# m921-submixer.net
KiCad netlist of a schematic drawn in EAGLE
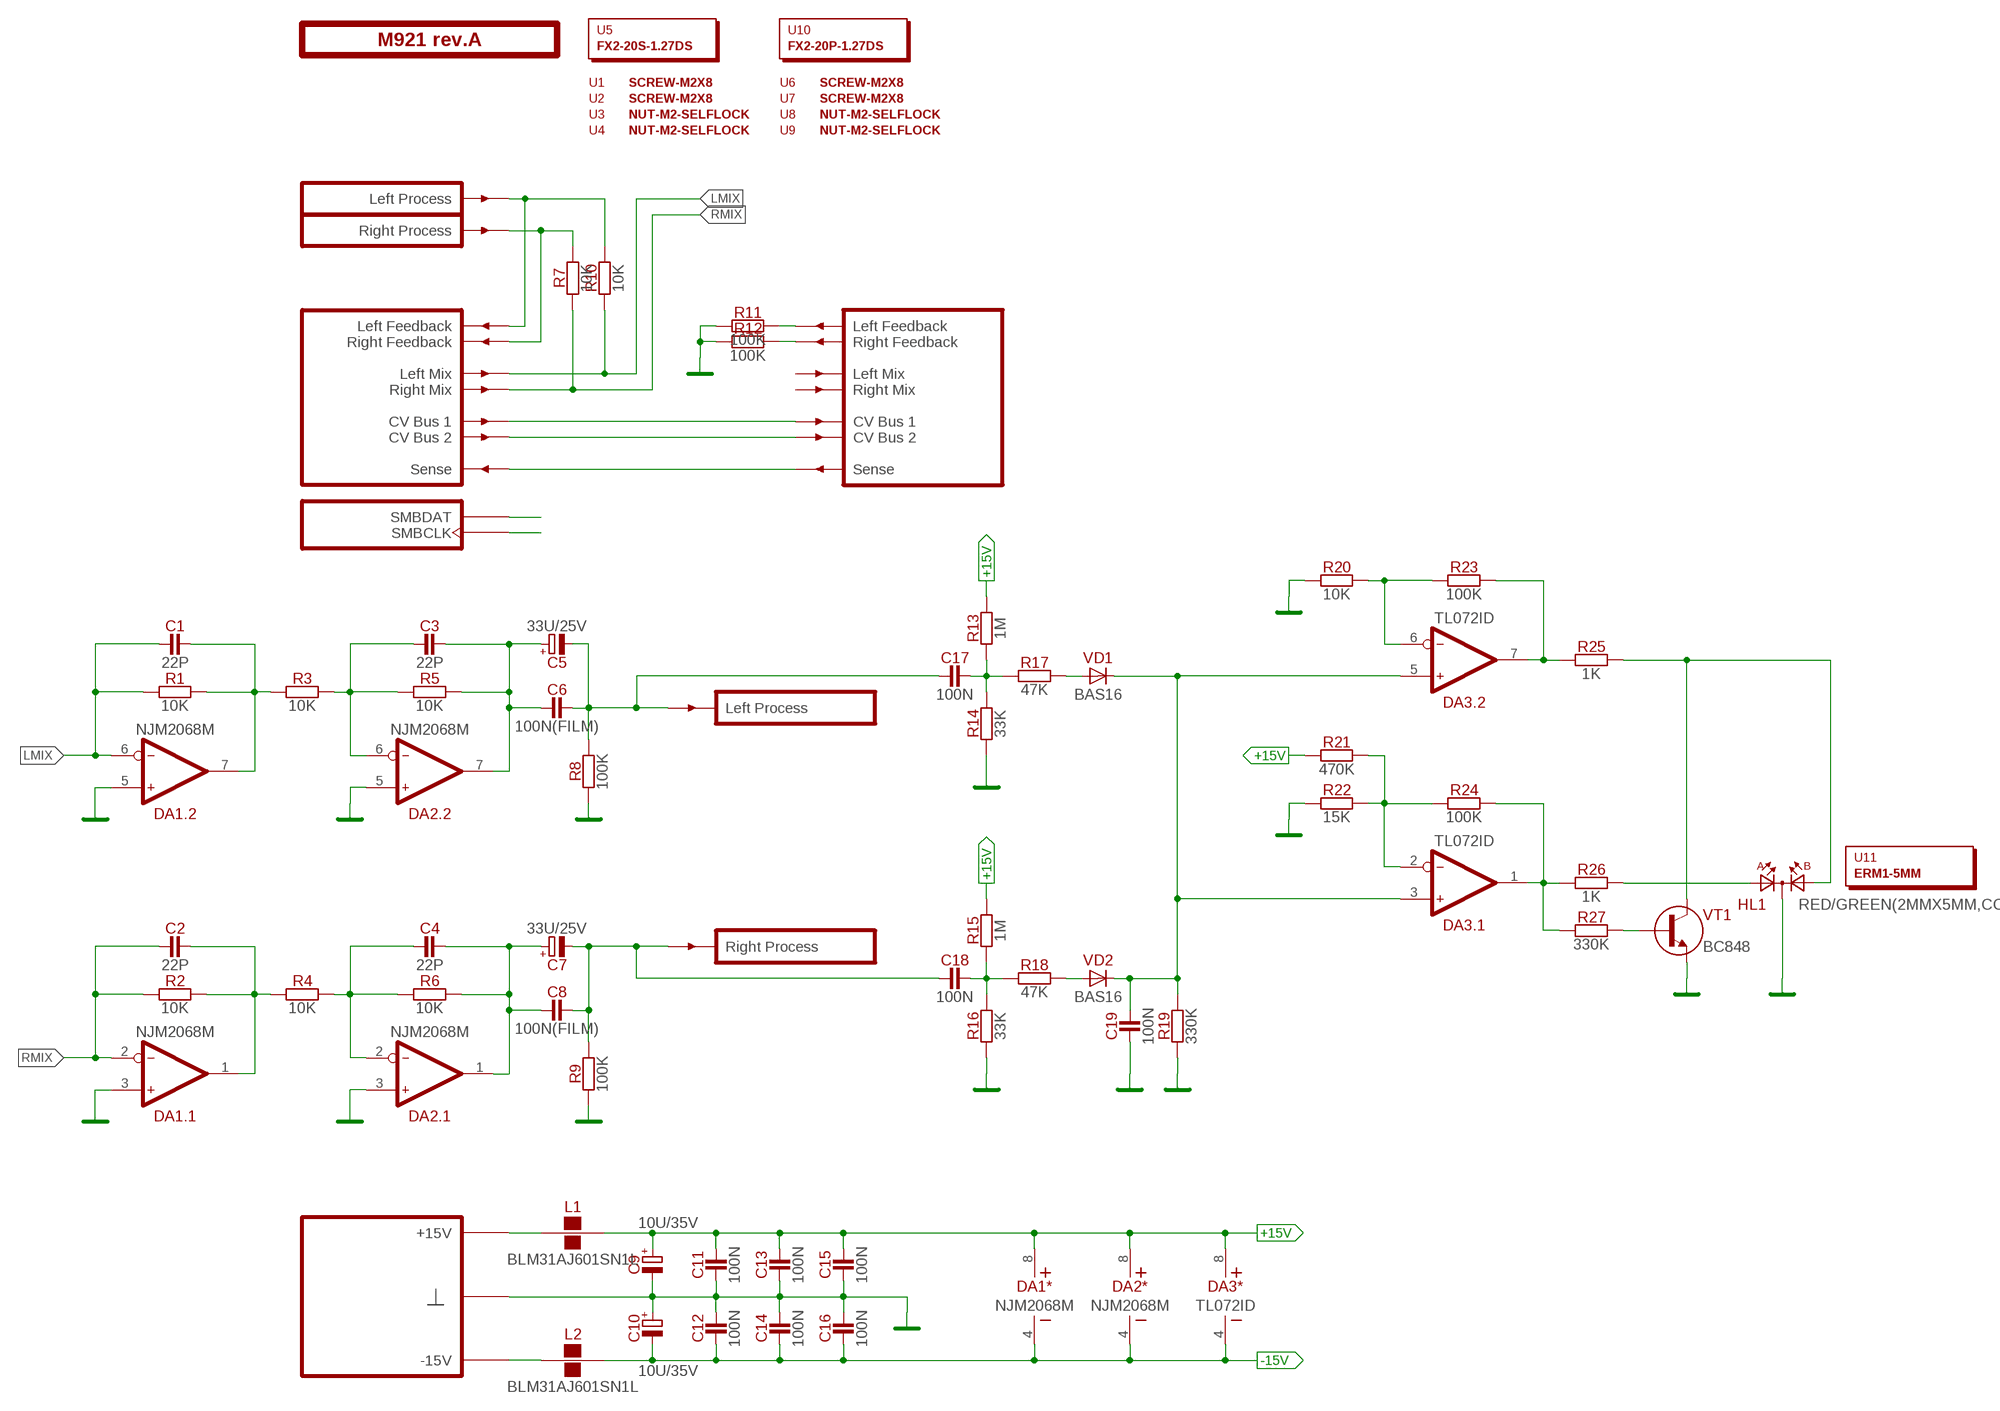
[diagram p0: schematic, sheet 1]

(export (version "E")
  (design (tool "Eeschema 10.0.6"))
  (components
    (comp (ref "C1")
      (value "22P")
      (footprint "eagle-import:C-0805")
      (libsource (lib "eagle-import") (part "?22P"))
    )
    (comp (ref "C2")
      (value "22P")
      (footprint "eagle-import:C-0805")
      (libsource (lib "eagle-import") (part "?22P"))
    )
    (comp (ref "C3")
      (value "22P")
      (footprint "eagle-import:C-0805")
      (libsource (lib "eagle-import") (part "?22P"))
    )
    (comp (ref "C4")
      (value "22P")
      (footprint "eagle-import:C-0805")
      (libsource (lib "eagle-import") (part "?22P"))
    )
    (comp (ref "C5")
      (value "33U/25V")
      (footprint "eagle-import:E2,5-7")
      (libsource (lib "eagle-import") (part "?33U/25V"))
    )
    (comp (ref "C6")
      (value "100N(FILM)")
      (footprint "eagle-import:C050-025X075")
      (libsource (lib "eagle-import") (part "?100N(FILM)"))
    )
    (comp (ref "C7")
      (value "33U/25V")
      (footprint "eagle-import:E2,5-7")
      (libsource (lib "eagle-import") (part "?33U/25V"))
    )
    (comp (ref "C8")
      (value "100N(FILM)")
      (footprint "eagle-import:C050-025X075")
      (libsource (lib "eagle-import") (part "?100N(FILM)"))
    )
    (comp (ref "C9")
      (value "10U/35V")
      (footprint "eagle-import:E2-5")
      (libsource (lib "eagle-import") (part "?10U/35V"))
    )
    (comp (ref "C10")
      (value "10U/35V")
      (footprint "eagle-import:E2-5")
      (libsource (lib "eagle-import") (part "?10U/35V"))
    )
    (comp (ref "C11")
      (value "100N")
      (footprint "eagle-import:C-0805")
      (libsource (lib "eagle-import") (part "?100N"))
    )
    (comp (ref "C12")
      (value "100N")
      (footprint "eagle-import:C-0805")
      (libsource (lib "eagle-import") (part "?100N"))
    )
    (comp (ref "C13")
      (value "100N")
      (footprint "eagle-import:C-0805")
      (libsource (lib "eagle-import") (part "?100N"))
    )
    (comp (ref "C14")
      (value "100N")
      (footprint "eagle-import:C-0805")
      (libsource (lib "eagle-import") (part "?100N"))
    )
    (comp (ref "C15")
      (value "100N")
      (footprint "eagle-import:C-0805")
      (libsource (lib "eagle-import") (part "?100N"))
    )
    (comp (ref "C16")
      (value "100N")
      (footprint "eagle-import:C-0805")
      (libsource (lib "eagle-import") (part "?100N"))
    )
    (comp (ref "C17")
      (value "100N")
      (footprint "eagle-import:C-0805")
      (libsource (lib "eagle-import") (part "?100N"))
    )
    (comp (ref "C18")
      (value "100N")
      (footprint "eagle-import:C-0805")
      (libsource (lib "eagle-import") (part "?100N"))
    )
    (comp (ref "C19")
      (value "100N")
      (footprint "eagle-import:C-0805")
      (libsource (lib "eagle-import") (part "?100N"))
    )
    (comp (ref "DA1")
      (value "NJM2068M")
      (footprint "eagle-import:SO-8")
      (libsource (lib "eagle-import") (part "NJM2068M"))
    )
    (comp (ref "DA2")
      (value "NJM2068M")
      (footprint "eagle-import:SO-8")
      (libsource (lib "eagle-import") (part "NJM2068M"))
    )
    (comp (ref "DA3")
      (value "TL072ID")
      (footprint "eagle-import:SO-8")
      (libsource (lib "eagle-import") (part "TL072ID"))
    )
    (comp (ref "HL1")
      (value "RED/GREEN(2MMX5MM,CC)")
      (footprint "eagle-import:LED2X5-3PIN")
      (libsource (lib "eagle-import") (part "?(2MMX5MM,CC)RED/GREEN"))
    )
    (comp (ref "L1")
      (value "BLM31AJ601SN1L")
      (footprint "eagle-import:1206")
      (libsource (lib "eagle-import") (part "BLM31AJ601SN1L"))
    )
    (comp (ref "L2")
      (value "BLM31AJ601SN1L")
      (footprint "eagle-import:1206")
      (libsource (lib "eagle-import") (part "BLM31AJ601SN1L"))
    )
    (comp (ref "PCB1")
      (value "M921 rev.A")
      (footprint "eagle-import:ST2-BOARD-26")
      (libsource (lib "eagle-import") (part "ST2-BOARD-?26"))
    )
    (comp (ref "R1")
      (value "10K")
      (footprint "eagle-import:R-0805")
      (libsource (lib "eagle-import") (part "?10K"))
    )
    (comp (ref "R2")
      (value "10K")
      (footprint "eagle-import:R-0805")
      (libsource (lib "eagle-import") (part "?10K"))
    )
    (comp (ref "R3")
      (value "10K")
      (footprint "eagle-import:R-0805")
      (libsource (lib "eagle-import") (part "?10K"))
    )
    (comp (ref "R4")
      (value "10K")
      (footprint "eagle-import:R-0805")
      (libsource (lib "eagle-import") (part "?10K"))
    )
    (comp (ref "R5")
      (value "10K")
      (footprint "eagle-import:R-0805")
      (libsource (lib "eagle-import") (part "?10K"))
    )
    (comp (ref "R6")
      (value "10K")
      (footprint "eagle-import:R-0805")
      (libsource (lib "eagle-import") (part "?10K"))
    )
    (comp (ref "R7")
      (value "10K")
      (footprint "eagle-import:R-0805")
      (libsource (lib "eagle-import") (part "?10K"))
    )
    (comp (ref "R8")
      (value "100K")
      (footprint "eagle-import:R-0805")
      (libsource (lib "eagle-import") (part "?100K"))
    )
    (comp (ref "R9")
      (value "100K")
      (footprint "eagle-import:R-0805")
      (libsource (lib "eagle-import") (part "?100K"))
    )
    (comp (ref "R10")
      (value "10K")
      (footprint "eagle-import:R-0805")
      (libsource (lib "eagle-import") (part "?10K"))
    )
    (comp (ref "R11")
      (value "100K")
      (footprint "eagle-import:R-0805")
      (libsource (lib "eagle-import") (part "?100K"))
    )
    (comp (ref "R12")
      (value "100K")
      (footprint "eagle-import:R-0805")
      (libsource (lib "eagle-import") (part "?100K"))
    )
    (comp (ref "R13")
      (value "1M")
      (footprint "eagle-import:R-0805")
      (libsource (lib "eagle-import") (part "?1M"))
    )
    (comp (ref "R14")
      (value "33K")
      (footprint "eagle-import:R-0805")
      (libsource (lib "eagle-import") (part "?33K"))
    )
    (comp (ref "R15")
      (value "1M")
      (footprint "eagle-import:R-0805")
      (libsource (lib "eagle-import") (part "?1M"))
    )
    (comp (ref "R16")
      (value "33K")
      (footprint "eagle-import:R-0805")
      (libsource (lib "eagle-import") (part "?33K"))
    )
    (comp (ref "R17")
      (value "47K")
      (footprint "eagle-import:R-0805")
      (libsource (lib "eagle-import") (part "?47K"))
    )
    (comp (ref "R18")
      (value "47K")
      (footprint "eagle-import:R-0805")
      (libsource (lib "eagle-import") (part "?47K"))
    )
    (comp (ref "R19")
      (value "330K")
      (footprint "eagle-import:R-0805")
      (libsource (lib "eagle-import") (part "?330K"))
    )
    (comp (ref "R20")
      (value "10K")
      (footprint "eagle-import:R-0805")
      (libsource (lib "eagle-import") (part "?10K"))
    )
    (comp (ref "R21")
      (value "470K")
      (footprint "eagle-import:R-0805")
      (libsource (lib "eagle-import") (part "?470K"))
    )
    (comp (ref "R22")
      (value "15K")
      (footprint "eagle-import:R-0805")
      (libsource (lib "eagle-import") (part "?15K"))
    )
    (comp (ref "R23")
      (value "100K")
      (footprint "eagle-import:R-0805")
      (libsource (lib "eagle-import") (part "?100K"))
    )
    (comp (ref "R24")
      (value "100K")
      (footprint "eagle-import:R-0805")
      (libsource (lib "eagle-import") (part "?100K"))
    )
    (comp (ref "R25")
      (value "1K")
      (footprint "eagle-import:R-0805")
      (libsource (lib "eagle-import") (part "?1K"))
    )
    (comp (ref "R26")
      (value "1K")
      (footprint "eagle-import:R-0805")
      (libsource (lib "eagle-import") (part "?1K"))
    )
    (comp (ref "R27")
      (value "330K")
      (footprint "eagle-import:R-0805")
      (libsource (lib "eagle-import") (part "?330K"))
    )
    (comp (ref "U1")
      (value "SCREW-M2X8")
      (footprint "eagle-import:EMPTY")
      (libsource (lib "eagle-import") (part "?SCREW-M2X8"))
    )
    (comp (ref "U2")
      (value "SCREW-M2X8")
      (footprint "eagle-import:EMPTY")
      (libsource (lib "eagle-import") (part "?SCREW-M2X8"))
    )
    (comp (ref "U3")
      (value "NUT-M2-SELFLOCK")
      (footprint "eagle-import:EMPTY")
      (libsource (lib "eagle-import") (part "?NUT-M2-SELFLOCK"))
    )
    (comp (ref "U4")
      (value "NUT-M2-SELFLOCK")
      (footprint "eagle-import:EMPTY")
      (libsource (lib "eagle-import") (part "?NUT-M2-SELFLOCK"))
    )
    (comp (ref "U5")
      (value "FX2-20S-1.27DS")
      (footprint "eagle-import:EMPTY")
      (libsource (lib "eagle-import") (part "?FX2-20S-1.27DS"))
    )
    (comp (ref "U6")
      (value "SCREW-M2X8")
      (footprint "eagle-import:EMPTY")
      (libsource (lib "eagle-import") (part "?SCREW-M2X8"))
    )
    (comp (ref "U7")
      (value "SCREW-M2X8")
      (footprint "eagle-import:EMPTY")
      (libsource (lib "eagle-import") (part "?SCREW-M2X8"))
    )
    (comp (ref "U8")
      (value "NUT-M2-SELFLOCK")
      (footprint "eagle-import:EMPTY")
      (libsource (lib "eagle-import") (part "?NUT-M2-SELFLOCK"))
    )
    (comp (ref "U9")
      (value "NUT-M2-SELFLOCK")
      (footprint "eagle-import:EMPTY")
      (libsource (lib "eagle-import") (part "?NUT-M2-SELFLOCK"))
    )
    (comp (ref "U10")
      (value "FX2-20P-1.27DS")
      (footprint "eagle-import:EMPTY")
      (libsource (lib "eagle-import") (part "?FX2-20P-1.27DS"))
    )
    (comp (ref "U11")
      (value "ERM1-5MM")
      (footprint "eagle-import:EMPTY")
      (libsource (lib "eagle-import") (part "?ERM1-5MM"))
    )
    (comp (ref "VD1")
      (value "BAS16")
      (footprint "eagle-import:SOT23")
      (libsource (lib "eagle-import") (part "?BAS16"))
    )
    (comp (ref "VD2")
      (value "BAS16")
      (footprint "eagle-import:SOT23")
      (libsource (lib "eagle-import") (part "?BAS16"))
    )
    (comp (ref "VT1")
      (value "BC848")
      (footprint "eagle-import:SOT23")
      (libsource (lib "eagle-import") (part "?BC848"))
    )
  )
  (nets
    (net (code "1") (name "+15V") (class "Default")
      (node (ref "C11") (pin "2") (pinfunction "2_2") (pintype "passive"))
      (node (ref "C13") (pin "2") (pinfunction "2_2") (pintype "passive"))
      (node (ref "C15") (pin "2") (pinfunction "2_2") (pintype "passive"))
      (node (ref "C9") (pin "+") (pinfunction "+_+") (pintype "passive"))
      (node (ref "DA1") (pin "8") (pinfunction "V+_8") (pintype "power_in"))
      (node (ref "DA2") (pin "8") (pinfunction "V+_8") (pintype "power_in"))
      (node (ref "DA3") (pin "8") (pinfunction "V+_8") (pintype "power_in"))
      (node (ref "L1") (pin "2") (pinfunction "2_2") (pintype "passive"))
      (node (ref "R13") (pin "2") (pinfunction "2_2") (pintype "passive"))
      (node (ref "R15") (pin "2") (pinfunction "2_2") (pintype "passive"))
      (node (ref "R21") (pin "1") (pinfunction "1_1") (pintype "passive"))
    )
    (net (code "2") (name "-15V") (class "Default")
      (node (ref "C10") (pin "-") (pinfunction "-_-") (pintype "passive"))
      (node (ref "C12") (pin "1") (pinfunction "1_1") (pintype "passive"))
      (node (ref "C14") (pin "1") (pinfunction "1_1") (pintype "passive"))
      (node (ref "C16") (pin "1") (pinfunction "1_1") (pintype "passive"))
      (node (ref "DA1") (pin "4") (pinfunction "V-_4") (pintype "power_in"))
      (node (ref "DA2") (pin "4") (pinfunction "V-_4") (pintype "power_in"))
      (node (ref "DA3") (pin "4") (pinfunction "V-_4") (pintype "power_in"))
      (node (ref "L2") (pin "2") (pinfunction "2_2") (pintype "passive"))
    )
    (net (code "3") (name "GND") (class "Default")
      (node (ref "C10") (pin "+") (pinfunction "+_+") (pintype "passive"))
      (node (ref "C11") (pin "1") (pinfunction "1_1") (pintype "passive"))
      (node (ref "C12") (pin "2") (pinfunction "2_2") (pintype "passive"))
      (node (ref "C13") (pin "1") (pinfunction "1_1") (pintype "passive"))
      (node (ref "C14") (pin "2") (pinfunction "2_2") (pintype "passive"))
      (node (ref "C15") (pin "1") (pinfunction "1_1") (pintype "passive"))
      (node (ref "C16") (pin "2") (pinfunction "2_2") (pintype "passive"))
      (node (ref "C19") (pin "1") (pinfunction "1_1") (pintype "passive"))
      (node (ref "C9") (pin "-") (pinfunction "-_-") (pintype "passive"))
      (node (ref "DA1") (pin "3") (pinfunction "IN+_3") (pintype "input"))
      (node (ref "DA1") (pin "5") (pinfunction "IN+_5") (pintype "input"))
      (node (ref "DA2") (pin "3") (pinfunction "IN+_3") (pintype "input"))
      (node (ref "DA2") (pin "5") (pinfunction "IN+_5") (pintype "input"))
      (node (ref "HL1") (pin "K") (pinfunction "K_K") (pintype "passive"))
      (node (ref "PCB1") (pin "B4") (pinfunction "GND_B4") (pintype "bidirectional"))
      (node (ref "PCB1") (pin "B4'") (pinfunction "GND_B4'") (pintype "bidirectional"))
      (node (ref "PCB1") (pin "B5") (pinfunction "GND_B5") (pintype "bidirectional"))
      (node (ref "PCB1") (pin "B5'") (pinfunction "GND_B5'") (pintype "bidirectional"))
      (node (ref "PCB1") (pin "B6") (pinfunction "GND_B6") (pintype "bidirectional"))
      (node (ref "PCB1") (pin "B6'") (pinfunction "GND_B6'") (pintype "bidirectional"))
      (node (ref "PCB1") (pin "B7") (pinfunction "GND_B7") (pintype "bidirectional"))
      (node (ref "PCB1") (pin "B7'") (pinfunction "GND_B7'") (pintype "bidirectional"))
      (node (ref "PCB1") (pin "B8") (pinfunction "GND_B8") (pintype "bidirectional"))
      (node (ref "PCB1") (pin "B8'") (pinfunction "GND_B8'") (pintype "bidirectional"))
      (node (ref "R11") (pin "1") (pinfunction "1_1") (pintype "passive"))
      (node (ref "R12") (pin "1") (pinfunction "1_1") (pintype "passive"))
      (node (ref "R14") (pin "1") (pinfunction "1_1") (pintype "passive"))
      (node (ref "R16") (pin "1") (pinfunction "1_1") (pintype "passive"))
      (node (ref "R19") (pin "1") (pinfunction "1_1") (pintype "passive"))
      (node (ref "R20") (pin "1") (pinfunction "1_1") (pintype "passive"))
      (node (ref "R22") (pin "1") (pinfunction "1_1") (pintype "passive"))
      (node (ref "R8") (pin "1") (pinfunction "1_1") (pintype "passive"))
      (node (ref "R9") (pin "1") (pinfunction "1_1") (pintype "passive"))
      (node (ref "VT1") (pin "2") (pinfunction "E_2") (pintype "passive"))
    )
    (net (code "4") (name "LMIX") (class "Default")
      (node (ref "C1") (pin "1") (pinfunction "1_1") (pintype "passive"))
      (node (ref "DA1") (pin "6") (pinfunction "IN-_6") (pintype "input"))
      (node (ref "PCB1") (pin "ALMIX") (pinfunction "LMIX_ALMIX") (pintype "bidirectional"))
      (node (ref "R1") (pin "1") (pinfunction "1_1") (pintype "passive"))
      (node (ref "R10") (pin "1") (pinfunction "1_1") (pintype "passive"))
    )
    (net (code "5") (name "Net-(C17-Pad2)") (class "Default")
      (node (ref "C17") (pin "2") (pinfunction "2_2") (pintype "passive"))
      (node (ref "R13") (pin "1") (pinfunction "1_1") (pintype "passive"))
      (node (ref "R14") (pin "2") (pinfunction "2_2") (pintype "passive"))
      (node (ref "R17") (pin "1") (pinfunction "1_1") (pintype "passive"))
    )
    (net (code "6") (name "Net-(C18-Pad2)") (class "Default")
      (node (ref "C18") (pin "2") (pinfunction "2_2") (pintype "passive"))
      (node (ref "R15") (pin "1") (pinfunction "1_1") (pintype "passive"))
      (node (ref "R16") (pin "2") (pinfunction "2_2") (pintype "passive"))
      (node (ref "R18") (pin "1") (pinfunction "1_1") (pintype "passive"))
    )
    (net (code "7") (name "Net-(DA1B-OUT)") (class "Default")
      (node (ref "C2") (pin "2") (pinfunction "2_2") (pintype "passive"))
      (node (ref "DA1") (pin "1") (pinfunction "OUT_1") (pintype "output"))
      (node (ref "R2") (pin "2") (pinfunction "2_2") (pintype "passive"))
      (node (ref "R4") (pin "1") (pinfunction "1_1") (pintype "passive"))
    )
    (net (code "8") (name "Net-(DA1C-OUT)") (class "Default")
      (node (ref "C1") (pin "2") (pinfunction "2_2") (pintype "passive"))
      (node (ref "DA1") (pin "7") (pinfunction "OUT_7") (pintype "output"))
      (node (ref "R1") (pin "2") (pinfunction "2_2") (pintype "passive"))
      (node (ref "R3") (pin "1") (pinfunction "1_1") (pintype "passive"))
    )
    (net (code "9") (name "Net-(DA2B-IN-)") (class "Default")
      (node (ref "C4") (pin "1") (pinfunction "1_1") (pintype "passive"))
      (node (ref "DA2") (pin "2") (pinfunction "IN-_2") (pintype "input"))
      (node (ref "R4") (pin "2") (pinfunction "2_2") (pintype "passive"))
      (node (ref "R6") (pin "1") (pinfunction "1_1") (pintype "passive"))
    )
    (net (code "10") (name "Net-(DA2B-OUT)") (class "Default")
      (node (ref "C4") (pin "2") (pinfunction "2_2") (pintype "passive"))
      (node (ref "C7") (pin "+") (pinfunction "+_+") (pintype "passive"))
      (node (ref "C8") (pin "1") (pinfunction "1_1") (pintype "passive"))
      (node (ref "DA2") (pin "1") (pinfunction "OUT_1") (pintype "output"))
      (node (ref "R6") (pin "2") (pinfunction "2_2") (pintype "passive"))
    )
    (net (code "11") (name "Net-(DA2C-IN-)") (class "Default")
      (node (ref "C3") (pin "1") (pinfunction "1_1") (pintype "passive"))
      (node (ref "DA2") (pin "6") (pinfunction "IN-_6") (pintype "input"))
      (node (ref "R3") (pin "2") (pinfunction "2_2") (pintype "passive"))
      (node (ref "R5") (pin "1") (pinfunction "1_1") (pintype "passive"))
    )
    (net (code "12") (name "Net-(DA2C-OUT)") (class "Default")
      (node (ref "C3") (pin "2") (pinfunction "2_2") (pintype "passive"))
      (node (ref "C5") (pin "+") (pinfunction "+_+") (pintype "passive"))
      (node (ref "C6") (pin "1") (pinfunction "1_1") (pintype "passive"))
      (node (ref "DA2") (pin "7") (pinfunction "OUT_7") (pintype "output"))
      (node (ref "R5") (pin "2") (pinfunction "2_2") (pintype "passive"))
    )
    (net (code "13") (name "Net-(DA3B-IN+)") (class "Default")
      (node (ref "C19") (pin "2") (pinfunction "2_2") (pintype "passive"))
      (node (ref "DA3") (pin "3") (pinfunction "IN+_3") (pintype "input"))
      (node (ref "DA3") (pin "5") (pinfunction "IN+_5") (pintype "input"))
      (node (ref "R19") (pin "2") (pinfunction "2_2") (pintype "passive"))
      (node (ref "VD1") (pin "2") (pinfunction "C_2") (pintype "passive"))
      (node (ref "VD2") (pin "2") (pinfunction "C_2") (pintype "passive"))
    )
    (net (code "14") (name "Net-(DA3B-IN-)") (class "Default")
      (node (ref "DA3") (pin "2") (pinfunction "IN-_2") (pintype "input"))
      (node (ref "R21") (pin "2") (pinfunction "2_2") (pintype "passive"))
      (node (ref "R22") (pin "2") (pinfunction "2_2") (pintype "passive"))
      (node (ref "R24") (pin "1") (pinfunction "1_1") (pintype "passive"))
    )
    (net (code "15") (name "Net-(DA3B-OUT)") (class "Default")
      (node (ref "DA3") (pin "1") (pinfunction "OUT_1") (pintype "output"))
      (node (ref "R24") (pin "2") (pinfunction "2_2") (pintype "passive"))
      (node (ref "R26") (pin "1") (pinfunction "1_1") (pintype "passive"))
      (node (ref "R27") (pin "1") (pinfunction "1_1") (pintype "passive"))
    )
    (net (code "16") (name "Net-(DA3C-IN-)") (class "Default")
      (node (ref "DA3") (pin "6") (pinfunction "IN-_6") (pintype "input"))
      (node (ref "R20") (pin "2") (pinfunction "2_2") (pintype "passive"))
      (node (ref "R23") (pin "1") (pinfunction "1_1") (pintype "passive"))
    )
    (net (code "17") (name "Net-(DA3C-OUT)") (class "Default")
      (node (ref "DA3") (pin "7") (pinfunction "OUT_7") (pintype "output"))
      (node (ref "R23") (pin "2") (pinfunction "2_2") (pintype "passive"))
      (node (ref "R25") (pin "1") (pinfunction "1_1") (pintype "passive"))
    )
    (net (code "18") (name "Net-(HL1-PadA1)") (class "Default")
      (node (ref "HL1") (pin "A1") (pinfunction "A1_A1") (pintype "passive"))
      (node (ref "R26") (pin "2") (pinfunction "2_2") (pintype "passive"))
    )
    (net (code "19") (name "Net-(L1-Pad1)") (class "Default")
      (node (ref "L1") (pin "1") (pinfunction "1_1") (pintype "passive"))
      (node (ref "PCB1") (pin "A+15") (pinfunction "P+15V_A+15") (pintype "bidirectional"))
      (node (ref "PCB1") (pin "A+15'") (pinfunction "P+15V_A+15'") (pintype "bidirectional"))
      (node (ref "PCB1") (pin "B+15") (pinfunction "P+15V_B+15") (pintype "bidirectional"))
      (node (ref "PCB1") (pin "B+15'") (pinfunction "P+15V_B+15'") (pintype "bidirectional"))
    )
    (net (code "20") (name "Net-(L2-Pad1)") (class "Default")
      (node (ref "L2") (pin "1") (pinfunction "1_1") (pintype "passive"))
      (node (ref "PCB1") (pin "A-15") (pinfunction "P-15V_A-15") (pintype "bidirectional"))
      (node (ref "PCB1") (pin "A-15'") (pinfunction "P-15V_A-15'") (pintype "bidirectional"))
      (node (ref "PCB1") (pin "B-15") (pinfunction "P-15V_B-15") (pintype "bidirectional"))
      (node (ref "PCB1") (pin "B-15'") (pinfunction "P-15V_B-15'") (pintype "bidirectional"))
    )
    (net (code "21") (name "Net-(PCB1B-INL)") (class "Default")
      (node (ref "PCB1") (pin "ALFBK") (pinfunction "LFBK_ALFBK") (pintype "bidirectional"))
      (node (ref "PCB1") (pin "BINL") (pinfunction "INL_BINL") (pintype "bidirectional"))
      (node (ref "R10") (pin "2") (pinfunction "2_2") (pintype "passive"))
    )
    (net (code "22") (name "Net-(PCB1C-INR)") (class "Default")
      (node (ref "PCB1") (pin "ARFBK") (pinfunction "RFBK_ARFBK") (pintype "bidirectional"))
      (node (ref "PCB1") (pin "BINR") (pinfunction "INR_BINR") (pintype "bidirectional"))
      (node (ref "R7") (pin "2") (pinfunction "2_2") (pintype "passive"))
    )
    (net (code "23") (name "Net-(PCB1D-OUTL)") (class "Default")
      (node (ref "C17") (pin "1") (pinfunction "1_1") (pintype "passive"))
      (node (ref "C5") (pin "-") (pinfunction "-_-") (pintype "passive"))
      (node (ref "C6") (pin "2") (pinfunction "2_2") (pintype "passive"))
      (node (ref "PCB1") (pin "BOUTL'") (pinfunction "OUTL_BOUTL'") (pintype "bidirectional"))
      (node (ref "R8") (pin "2") (pinfunction "2_2") (pintype "passive"))
    )
    (net (code "24") (name "Net-(PCB1E-OUTR)") (class "Default")
      (node (ref "C18") (pin "1") (pinfunction "1_1") (pintype "passive"))
      (node (ref "C7") (pin "-") (pinfunction "-_-") (pintype "passive"))
      (node (ref "C8") (pin "2") (pinfunction "2_2") (pintype "passive"))
      (node (ref "PCB1") (pin "BOUTR'") (pinfunction "OUTR_BOUTR'") (pintype "bidirectional"))
      (node (ref "R9") (pin "2") (pinfunction "2_2") (pintype "passive"))
    )
    (net (code "25") (name "Net-(PCB1F-CV1)") (class "Default")
      (node (ref "PCB1") (pin "ACV1") (pinfunction "CV1_ACV1") (pintype "bidirectional"))
      (node (ref "PCB1") (pin "ACV1'") (pinfunction "CV1'_ACV1'") (pintype "bidirectional"))
    )
    (net (code "26") (name "Net-(PCB1F-CV2)") (class "Default")
      (node (ref "PCB1") (pin "ACV2") (pinfunction "CV2_ACV2") (pintype "bidirectional"))
      (node (ref "PCB1") (pin "ACV2'") (pinfunction "CV2'_ACV2'") (pintype "bidirectional"))
    )
    (net (code "27") (name "Net-(PCB1F-SENSE)") (class "Default")
      (node (ref "PCB1") (pin "BSENSE") (pinfunction "SENSE_BSENSE") (pintype "bidirectional"))
      (node (ref "PCB1") (pin "BSENSE'") (pinfunction "SENSE'_BSENSE'") (pintype "bidirectional"))
    )
    (net (code "28") (name "Net-(PCB1G-LFBK')") (class "Default")
      (node (ref "PCB1") (pin "ALFBK'") (pinfunction "LFBK'_ALFBK'") (pintype "bidirectional"))
      (node (ref "R11") (pin "2") (pinfunction "2_2") (pintype "passive"))
    )
    (net (code "29") (name "Net-(PCB1G-RFBK')") (class "Default")
      (node (ref "PCB1") (pin "ARFBK'") (pinfunction "RFBK'_ARFBK'") (pintype "bidirectional"))
      (node (ref "R12") (pin "2") (pinfunction "2_2") (pintype "passive"))
    )
    (net (code "30") (name "Net-(PCB1H-SMBCLK-PadASMBCLK')") (class "Default")
      (node (ref "PCB1") (pin "ASMBCLK") (pinfunction "SMBCLK_ASMBCLK") (pintype "bidirectional"))
      (node (ref "PCB1") (pin "ASMBCLK'") (pinfunction "SMBCLK_ASMBCLK'") (pintype "bidirectional"))
    )
    (net (code "31") (name "Net-(PCB1H-SMBDAT-PadASMBDAT')") (class "Default")
      (node (ref "PCB1") (pin "ASMBDAT") (pinfunction "SMBDAT_ASMBDAT") (pintype "bidirectional"))
      (node (ref "PCB1") (pin "ASMBDAT'") (pinfunction "SMBDAT_ASMBDAT'") (pintype "bidirectional"))
    )
    (net (code "32") (name "Net-(VD1-A)") (class "Default")
      (node (ref "R17") (pin "2") (pinfunction "2_2") (pintype "passive"))
      (node (ref "VD1") (pin "1") (pinfunction "A_1") (pintype "passive"))
    )
    (net (code "33") (name "Net-(VD2-A)") (class "Default")
      (node (ref "R18") (pin "2") (pinfunction "2_2") (pintype "passive"))
      (node (ref "VD2") (pin "1") (pinfunction "A_1") (pintype "passive"))
    )
    (net (code "34") (name "Net-(VT1-B)") (class "Default")
      (node (ref "R27") (pin "2") (pinfunction "2_2") (pintype "passive"))
      (node (ref "VT1") (pin "1") (pinfunction "B_1") (pintype "passive"))
    )
    (net (code "35") (name "Net-(VT1-C)") (class "Default")
      (node (ref "HL1") (pin "A2") (pinfunction "A2_A2") (pintype "passive"))
      (node (ref "R25") (pin "2") (pinfunction "2_2") (pintype "passive"))
      (node (ref "VT1") (pin "3") (pinfunction "C_3") (pintype "passive"))
    )
    (net (code "36") (name "RMIX") (class "Default")
      (node (ref "C2") (pin "1") (pinfunction "1_1") (pintype "passive"))
      (node (ref "DA1") (pin "2") (pinfunction "IN-_2") (pintype "input"))
      (node (ref "PCB1") (pin "ARMIX") (pinfunction "RMIX_ARMIX") (pintype "bidirectional"))
      (node (ref "R2") (pin "1") (pinfunction "1_1") (pintype "passive"))
      (node (ref "R7") (pin "1") (pinfunction "1_1") (pintype "passive"))
    )
    (net (code "37") (name "unconnected-(PCB1G-LMIX'-PadALMIX')") (class "Default")
      (node (ref "PCB1") (pin "ALMIX'") (pinfunction "LMIX'_ALMIX'") (pintype "bidirectional"))
    )
    (net (code "38") (name "unconnected-(PCB1G-RMIX'-PadARMIX')") (class "Default")
      (node (ref "PCB1") (pin "ARMIX'") (pinfunction "RMIX'_ARMIX'") (pintype "bidirectional"))
    )
  )
)
